# master_pi.net
KiCad netlist of a schematic drawn in EAGLE
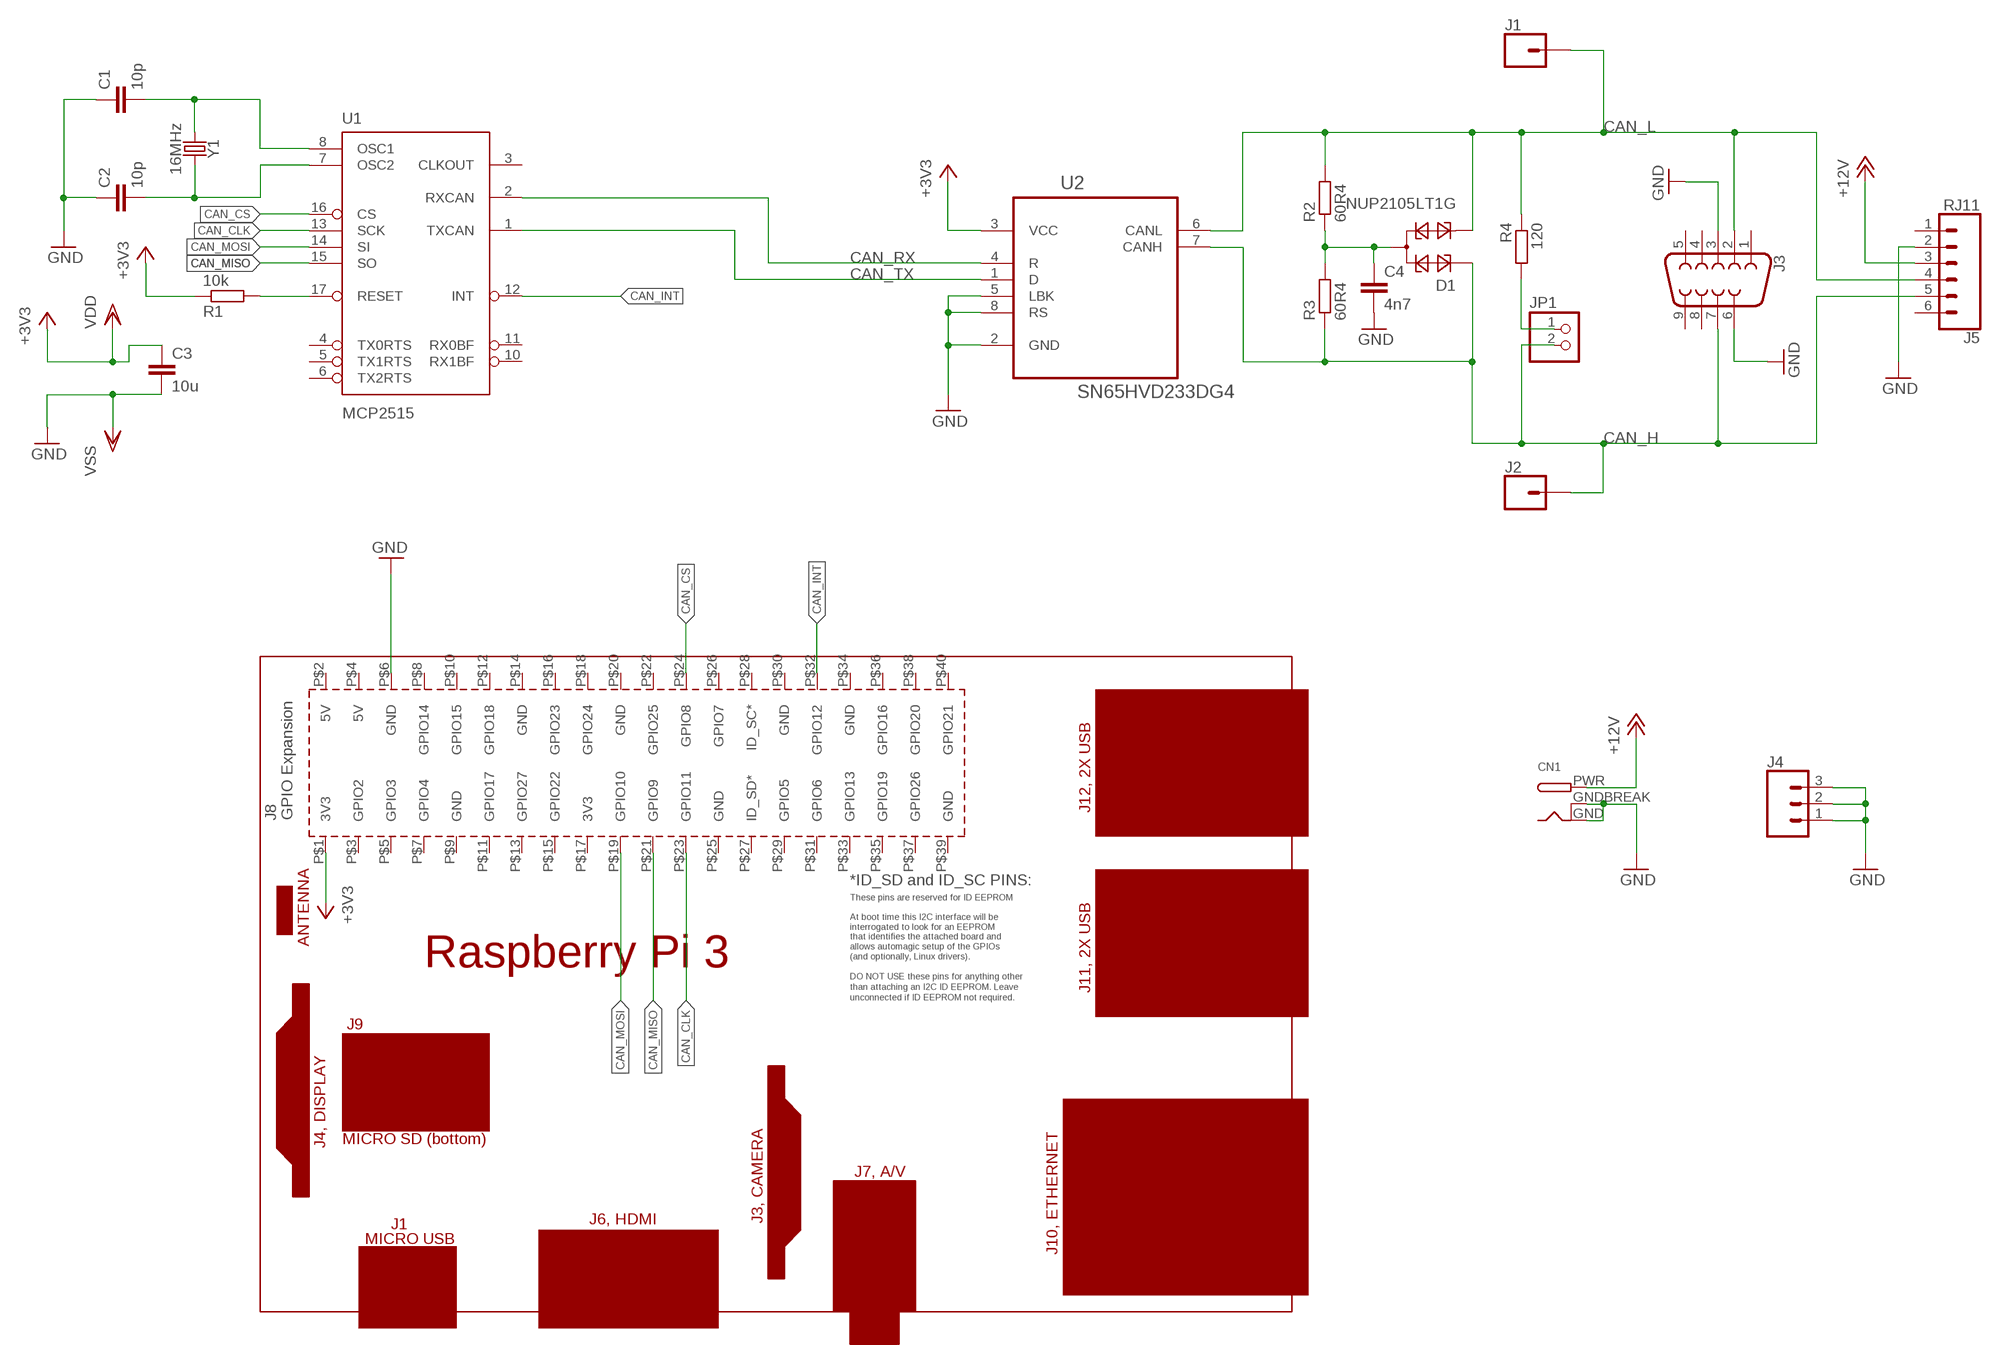
[diagram p0: schematic, sheet 1]

(export (version "E")
  (design (tool "Eeschema 10.0.6"))
  (components
    (comp (ref "C1")
      (value "10p")
      (footprint "eagle-import:C1206")
      (libsource (lib "eagle-import") (part "C-EUC1206"))
    )
    (comp (ref "C2")
      (value "10p")
      (footprint "eagle-import:C1206")
      (libsource (lib "eagle-import") (part "C-EUC1206"))
    )
    (comp (ref "C3")
      (value "10u")
      (footprint "eagle-import:C1206")
      (libsource (lib "eagle-import") (part "C-EUC1206"))
    )
    (comp (ref "C4")
      (value "4n7")
      (footprint "eagle-import:C1206")
      (libsource (lib "eagle-import") (part "C-EUC1206"))
    )
    (comp (ref "CN1")
      (value "DCBARRELPTH")
      (footprint "eagle-import:DCJACK_2MM_PTH")
      (libsource (lib "eagle-import") (part "DCBARRELPTH"))
    )
    (comp (ref "D1")
      (value "NUP2105LT1G")
      (footprint "eagle-import:SOT23")
      (libsource (lib "eagle-import") (part "PESD1CAN"))
    )
    (comp (ref "J1")
      (value "CONN_01")
      (footprint "eagle-import:1X01")
      (libsource (lib "eagle-import") (part "CONN_01"))
    )
    (comp (ref "J2")
      (value "CONN_01")
      (footprint "eagle-import:1X01")
      (libsource (lib "eagle-import") (part "CONN_01"))
    )
    (comp (ref "J3")
      (value "DB9FEMALE")
      (footprint "eagle-import:DB9")
      (libsource (lib "eagle-import") (part "DB9FEMALE"))
    )
    (comp (ref "J4")
      (value "CONN_03")
      (footprint "eagle-import:1X03")
      (libsource (lib "eagle-import") (part "CONN_03"))
    )
    (comp (ref "J5")
      (value "RJ11")
      (footprint "eagle-import:RJ11-6")
      (libsource (lib "eagle-import") (part "RJ11-6"))
    )
    (comp (ref "JP1")
      (value "PINHD-1X2")
      (footprint "eagle-import:1X02")
      (libsource (lib "eagle-import") (part "PINHD-1X2"))
    )
    (comp (ref "PCB1")
      (value "RPI3")
      (footprint "eagle-import:RPI3")
      (libsource (lib "eagle-import") (part "RPI3"))
    )
    (comp (ref "R1")
      (value "10k")
      (footprint "eagle-import:R1206")
      (libsource (lib "eagle-import") (part "R-EU_R1206"))
    )
    (comp (ref "R2")
      (value "60R4")
      (footprint "eagle-import:R1206")
      (libsource (lib "eagle-import") (part "R-EU_R1206"))
    )
    (comp (ref "R3")
      (value "60R4")
      (footprint "eagle-import:R1206")
      (libsource (lib "eagle-import") (part "R-EU_R1206"))
    )
    (comp (ref "R4")
      (value "120")
      (footprint "eagle-import:R1206")
      (libsource (lib "eagle-import") (part "R-EU_R1206"))
    )
    (comp (ref "U1")
      (value "MCP2515")
      (footprint "eagle-import:SO18W")
      (libsource (lib "eagle-import") (part "MCP2515(MCP2510)SO"))
    )
    (comp (ref "U2")
      (value "SN65HVD233DG4")
      (footprint "eagle-import:SOIC127P600X175-8N")
      (libsource (lib "eagle-import") (part "SN65HVD233DG4"))
    )
    (comp (ref "Y1")
      (value "16MHz")
      (footprint "eagle-import:HC49US")
      (libsource (lib "eagle-import") (part "CRYSTAL-16MHZPTH-HC49US"))
    )
  )
  (nets
    (net (code "1") (name "+3V3") (class "Default")
      (node (ref "C3") (pin "1") (pinfunction "1_1") (pintype "passive"))
      (node (ref "PCB1") (pin "P$1") (pinfunction "3V3_P$1") (pintype "bidirectional"))
      (node (ref "R1") (pin "1") (pinfunction "1_1") (pintype "passive"))
      (node (ref "U2") (pin "3") (pinfunction "VCC_3") (pintype "power_in"))
    )
    (net (code "2") (name "+12V") (class "Default")
      (node (ref "CN1") (pin "PWR") (pinfunction "PWR_PWR") (pintype "power_in"))
      (node (ref "J5") (pin "3") (pinfunction "3_3") (pintype "passive"))
    )
    (net (code "3") (name "/CAN_H") (class "Default")
      (node (ref "D1") (pin "1") (pinfunction "1_1") (pintype "passive"))
      (node (ref "J2") (pin "1") (pinfunction "1_1") (pintype "passive"))
      (node (ref "J3") (pin "7") (pinfunction "7_7") (pintype "passive"))
      (node (ref "J5") (pin "5") (pinfunction "5_5") (pintype "passive"))
      (node (ref "JP1") (pin "2") (pinfunction "2_2") (pintype "passive"))
      (node (ref "R3") (pin "1") (pinfunction "1_1") (pintype "passive"))
      (node (ref "U2") (pin "7") (pinfunction "CANH_7") (pintype "output"))
    )
    (net (code "4") (name "/CAN_L") (class "Default")
      (node (ref "D1") (pin "2") (pinfunction "2_2") (pintype "passive"))
      (node (ref "J1") (pin "1") (pinfunction "1_1") (pintype "passive"))
      (node (ref "J3") (pin "2") (pinfunction "2_2") (pintype "passive"))
      (node (ref "J5") (pin "4") (pinfunction "4_4") (pintype "passive"))
      (node (ref "R2") (pin "2") (pinfunction "2_2") (pintype "passive"))
      (node (ref "R4") (pin "1") (pinfunction "1_1") (pintype "passive"))
      (node (ref "U2") (pin "6") (pinfunction "CANL_6") (pintype "output"))
    )
    (net (code "5") (name "/CAN_RX") (class "Default")
      (node (ref "U1") (pin "2") (pinfunction "RXCAN_2") (pintype "input"))
      (node (ref "U2") (pin "4") (pinfunction "R_4") (pintype "input"))
    )
    (net (code "6") (name "/CAN_TX") (class "Default")
      (node (ref "U1") (pin "1") (pinfunction "TXCAN_1") (pintype "output"))
      (node (ref "U2") (pin "1") (pinfunction "D_1") (pintype "input"))
    )
    (net (code "7") (name "CAN_CLK") (class "Default")
      (node (ref "PCB1") (pin "P$23") (pinfunction "GPIO11_P$23") (pintype "bidirectional"))
      (node (ref "U1") (pin "13") (pinfunction "SCK_13") (pintype "input"))
    )
    (net (code "8") (name "CAN_CS") (class "Default")
      (node (ref "PCB1") (pin "P$24") (pinfunction "GPIO8_P$24") (pintype "bidirectional"))
      (node (ref "U1") (pin "16") (pinfunction "CS_16") (pintype "input"))
    )
    (net (code "9") (name "CAN_INT") (class "Default")
      (node (ref "PCB1") (pin "P$32") (pinfunction "GPIO12_P$32") (pintype "bidirectional"))
      (node (ref "U1") (pin "12") (pinfunction "INT_12") (pintype "output"))
    )
    (net (code "10") (name "CAN_MISO") (class "Default")
      (node (ref "PCB1") (pin "P$21") (pinfunction "GPIO9_P$21") (pintype "bidirectional"))
      (node (ref "U1") (pin "15") (pinfunction "SO_15") (pintype "output"))
    )
    (net (code "11") (name "CAN_MOSI") (class "Default")
      (node (ref "PCB1") (pin "P$19") (pinfunction "GPIO10_P$19") (pintype "bidirectional"))
      (node (ref "U1") (pin "14") (pinfunction "SI_14") (pintype "input"))
    )
    (net (code "12") (name "GND") (class "Default")
      (node (ref "C1") (pin "1") (pinfunction "1_1") (pintype "passive"))
      (node (ref "C2") (pin "1") (pinfunction "1_1") (pintype "passive"))
      (node (ref "C3") (pin "2") (pinfunction "2_2") (pintype "passive"))
      (node (ref "C4") (pin "2") (pinfunction "2_2") (pintype "passive"))
      (node (ref "CN1") (pin "GND") (pinfunction "GND_GND") (pintype "power_in"))
      (node (ref "CN1") (pin "GNDBREAK") (pinfunction "GNDBREAK_GNDBREAK") (pintype "power_in"))
      (node (ref "J3") (pin "3") (pinfunction "3_3") (pintype "passive"))
      (node (ref "J3") (pin "6") (pinfunction "6_6") (pintype "passive"))
      (node (ref "J4") (pin "1") (pinfunction "1_1") (pintype "passive"))
      (node (ref "J4") (pin "2") (pinfunction "2_2") (pintype "passive"))
      (node (ref "J4") (pin "3") (pinfunction "3_3") (pintype "passive"))
      (node (ref "J5") (pin "2") (pinfunction "2_2") (pintype "passive"))
      (node (ref "PCB1") (pin "P$6") (pinfunction "GND_P$6") (pintype "bidirectional"))
      (node (ref "U2") (pin "2") (pinfunction "GND_2") (pintype "passive"))
      (node (ref "U2") (pin "5") (pinfunction "LBK_5") (pintype "passive"))
      (node (ref "U2") (pin "8") (pinfunction "RS_8") (pintype "input"))
    )
    (net (code "13") (name "Net-(C4-Pad1)") (class "Default")
      (node (ref "C4") (pin "1") (pinfunction "1_1") (pintype "passive"))
      (node (ref "D1") (pin "3") (pinfunction "3_3") (pintype "passive"))
      (node (ref "R2") (pin "1") (pinfunction "1_1") (pintype "passive"))
      (node (ref "R3") (pin "2") (pinfunction "2_2") (pintype "passive"))
    )
    (net (code "14") (name "Net-(JP1-Pad1)") (class "Default")
      (node (ref "JP1") (pin "1") (pinfunction "1_1") (pintype "passive"))
      (node (ref "R4") (pin "2") (pinfunction "2_2") (pintype "passive"))
    )
    (net (code "15") (name "Net-(U1A-OSC1)") (class "Default")
      (node (ref "C1") (pin "2") (pinfunction "2_2") (pintype "passive"))
      (node (ref "U1") (pin "8") (pinfunction "OSC1_8") (pintype "input"))
      (node (ref "Y1") (pin "1") (pinfunction "1_1") (pintype "passive"))
    )
    (net (code "16") (name "Net-(U1A-OSC2)") (class "Default")
      (node (ref "C2") (pin "2") (pinfunction "2_2") (pintype "passive"))
      (node (ref "U1") (pin "7") (pinfunction "OSC2_7") (pintype "output"))
      (node (ref "Y1") (pin "2") (pinfunction "2_2") (pintype "passive"))
    )
    (net (code "17") (name "Net-(U1A-RESET)") (class "Default")
      (node (ref "R1") (pin "2") (pinfunction "2_2") (pintype "passive"))
      (node (ref "U1") (pin "17") (pinfunction "RESET_17") (pintype "input"))
    )
    (net (code "18") (name "unconnected-(J3-Pad1)") (class "Default")
      (node (ref "J3") (pin "1") (pinfunction "1_1") (pintype "passive"))
    )
    (net (code "19") (name "unconnected-(J3-Pad4)") (class "Default")
      (node (ref "J3") (pin "4") (pinfunction "4_4") (pintype "passive"))
    )
    (net (code "20") (name "unconnected-(J3-Pad5)") (class "Default")
      (node (ref "J3") (pin "5") (pinfunction "5_5") (pintype "passive"))
    )
    (net (code "21") (name "unconnected-(J3-Pad8)") (class "Default")
      (node (ref "J3") (pin "8") (pinfunction "8_8") (pintype "passive"))
    )
    (net (code "22") (name "unconnected-(J3-Pad9)") (class "Default")
      (node (ref "J3") (pin "9") (pinfunction "9_9") (pintype "passive"))
    )
    (net (code "23") (name "unconnected-(J5-Pad1)") (class "Default")
      (node (ref "J5") (pin "1") (pinfunction "1_1") (pintype "passive"))
    )
    (net (code "24") (name "unconnected-(J5-Pad6)") (class "Default")
      (node (ref "J5") (pin "6") (pinfunction "6_6") (pintype "passive"))
    )
    (net (code "25") (name "unconnected-(PCB1-3V3-PadP$17)") (class "Default")
      (node (ref "PCB1") (pin "P$17") (pinfunction "3V3_P$17") (pintype "bidirectional"))
    )
    (net (code "26") (name "unconnected-(PCB1-5V-PadP$2)") (class "Default")
      (node (ref "PCB1") (pin "P$2") (pinfunction "5V_P$2") (pintype "bidirectional"))
    )
    (net (code "27") (name "unconnected-(PCB1-5V-PadP$4)") (class "Default")
      (node (ref "PCB1") (pin "P$4") (pinfunction "5V_P$4") (pintype "bidirectional"))
    )
    (net (code "28") (name "unconnected-(PCB1-GND-PadP$9)") (class "Default")
      (node (ref "PCB1") (pin "P$9") (pinfunction "GND_P$9") (pintype "bidirectional"))
    )
    (net (code "29") (name "unconnected-(PCB1-GND-PadP$14)") (class "Default")
      (node (ref "PCB1") (pin "P$14") (pinfunction "GND_P$14") (pintype "bidirectional"))
    )
    (net (code "30") (name "unconnected-(PCB1-GND-PadP$20)") (class "Default")
      (node (ref "PCB1") (pin "P$20") (pinfunction "GND_P$20") (pintype "bidirectional"))
    )
    (net (code "31") (name "unconnected-(PCB1-GND-PadP$25)") (class "Default")
      (node (ref "PCB1") (pin "P$25") (pinfunction "GND_P$25") (pintype "bidirectional"))
    )
    (net (code "32") (name "unconnected-(PCB1-GND-PadP$30)") (class "Default")
      (node (ref "PCB1") (pin "P$30") (pinfunction "GND_P$30") (pintype "bidirectional"))
    )
    (net (code "33") (name "unconnected-(PCB1-GND-PadP$34)") (class "Default")
      (node (ref "PCB1") (pin "P$34") (pinfunction "GND_P$34") (pintype "bidirectional"))
    )
    (net (code "34") (name "unconnected-(PCB1-GND-PadP$39)") (class "Default")
      (node (ref "PCB1") (pin "P$39") (pinfunction "GND_P$39") (pintype "bidirectional"))
    )
    (net (code "35") (name "unconnected-(PCB1-GPIO2-PadP$3)") (class "Default")
      (node (ref "PCB1") (pin "P$3") (pinfunction "GPIO2_P$3") (pintype "bidirectional"))
    )
    (net (code "36") (name "unconnected-(PCB1-GPIO3-PadP$5)") (class "Default")
      (node (ref "PCB1") (pin "P$5") (pinfunction "GPIO3_P$5") (pintype "bidirectional"))
    )
    (net (code "37") (name "unconnected-(PCB1-GPIO4-PadP$7)") (class "Default")
      (node (ref "PCB1") (pin "P$7") (pinfunction "GPIO4_P$7") (pintype "bidirectional"))
    )
    (net (code "38") (name "unconnected-(PCB1-GPIO5-PadP$29)") (class "Default")
      (node (ref "PCB1") (pin "P$29") (pinfunction "GPIO5_P$29") (pintype "bidirectional"))
    )
    (net (code "39") (name "unconnected-(PCB1-GPIO6-PadP$31)") (class "Default")
      (node (ref "PCB1") (pin "P$31") (pinfunction "GPIO6_P$31") (pintype "bidirectional"))
    )
    (net (code "40") (name "unconnected-(PCB1-GPIO7-PadP$26)") (class "Default")
      (node (ref "PCB1") (pin "P$26") (pinfunction "GPIO7_P$26") (pintype "bidirectional"))
    )
    (net (code "41") (name "unconnected-(PCB1-GPIO13-PadP$33)") (class "Default")
      (node (ref "PCB1") (pin "P$33") (pinfunction "GPIO13_P$33") (pintype "bidirectional"))
    )
    (net (code "42") (name "unconnected-(PCB1-GPIO14-PadP$8)") (class "Default")
      (node (ref "PCB1") (pin "P$8") (pinfunction "GPIO14_P$8") (pintype "bidirectional"))
    )
    (net (code "43") (name "unconnected-(PCB1-GPIO15-PadP$10)") (class "Default")
      (node (ref "PCB1") (pin "P$10") (pinfunction "GPIO15_P$10") (pintype "bidirectional"))
    )
    (net (code "44") (name "unconnected-(PCB1-GPIO16-PadP$36)") (class "Default")
      (node (ref "PCB1") (pin "P$36") (pinfunction "GPIO16_P$36") (pintype "bidirectional"))
    )
    (net (code "45") (name "unconnected-(PCB1-GPIO17-PadP$11)") (class "Default")
      (node (ref "PCB1") (pin "P$11") (pinfunction "GPIO17_P$11") (pintype "bidirectional"))
    )
    (net (code "46") (name "unconnected-(PCB1-GPIO18-PadP$12)") (class "Default")
      (node (ref "PCB1") (pin "P$12") (pinfunction "GPIO18_P$12") (pintype "bidirectional"))
    )
    (net (code "47") (name "unconnected-(PCB1-GPIO19-PadP$35)") (class "Default")
      (node (ref "PCB1") (pin "P$35") (pinfunction "GPIO19_P$35") (pintype "bidirectional"))
    )
    (net (code "48") (name "unconnected-(PCB1-GPIO20-PadP$38)") (class "Default")
      (node (ref "PCB1") (pin "P$38") (pinfunction "GPIO20_P$38") (pintype "bidirectional"))
    )
    (net (code "49") (name "unconnected-(PCB1-GPIO21-PadP$40)") (class "Default")
      (node (ref "PCB1") (pin "P$40") (pinfunction "GPIO21_P$40") (pintype "bidirectional"))
    )
    (net (code "50") (name "unconnected-(PCB1-GPIO22-PadP$15)") (class "Default")
      (node (ref "PCB1") (pin "P$15") (pinfunction "GPIO22_P$15") (pintype "bidirectional"))
    )
    (net (code "51") (name "unconnected-(PCB1-GPIO23-PadP$16)") (class "Default")
      (node (ref "PCB1") (pin "P$16") (pinfunction "GPIO23_P$16") (pintype "bidirectional"))
    )
    (net (code "52") (name "unconnected-(PCB1-GPIO24-PadP$18)") (class "Default")
      (node (ref "PCB1") (pin "P$18") (pinfunction "GPIO24_P$18") (pintype "bidirectional"))
    )
    (net (code "53") (name "unconnected-(PCB1-GPIO25-PadP$22)") (class "Default")
      (node (ref "PCB1") (pin "P$22") (pinfunction "GPIO25_P$22") (pintype "bidirectional"))
    )
    (net (code "54") (name "unconnected-(PCB1-GPIO26-PadP$37)") (class "Default")
      (node (ref "PCB1") (pin "P$37") (pinfunction "GPIO26_P$37") (pintype "bidirectional"))
    )
    (net (code "55") (name "unconnected-(PCB1-GPIO27-PadP$13)") (class "Default")
      (node (ref "PCB1") (pin "P$13") (pinfunction "GPIO27_P$13") (pintype "bidirectional"))
    )
    (net (code "56") (name "unconnected-(PCB1-ID_SC*-PadP$28)") (class "Default")
      (node (ref "PCB1") (pin "P$28") (pinfunction "ID_SC*_P$28") (pintype "bidirectional"))
    )
    (net (code "57") (name "unconnected-(PCB1-ID_SD*-PadP$27)") (class "Default")
      (node (ref "PCB1") (pin "P$27") (pinfunction "ID_SD*_P$27") (pintype "bidirectional"))
    )
    (net (code "58") (name "unconnected-(U1A-CLKOUT-Pad3)") (class "Default")
      (node (ref "U1") (pin "3") (pinfunction "CLKOUT_3") (pintype "output"))
    )
    (net (code "59") (name "unconnected-(U1A-RX0BF-Pad11)") (class "Default")
      (node (ref "U1") (pin "11") (pinfunction "RX0BF_11") (pintype "output"))
    )
    (net (code "60") (name "unconnected-(U1A-RX1BF-Pad10)") (class "Default")
      (node (ref "U1") (pin "10") (pinfunction "RX1BF_10") (pintype "output"))
    )
    (net (code "61") (name "unconnected-(U1A-TX0RTS-Pad4)") (class "Default")
      (node (ref "U1") (pin "4") (pinfunction "TX0RTS_4") (pintype "input"))
    )
    (net (code "62") (name "unconnected-(U1A-TX1RTS-Pad5)") (class "Default")
      (node (ref "U1") (pin "5") (pinfunction "TX1RTS_5") (pintype "input"))
    )
    (net (code "63") (name "unconnected-(U1A-TX2RTS-Pad6)") (class "Default")
      (node (ref "U1") (pin "6") (pinfunction "TX2RTS_6") (pintype "input"))
    )
  )
)
